# cc_cv_charger.net
KiCad netlist of a schematic drawn in Altium Designer
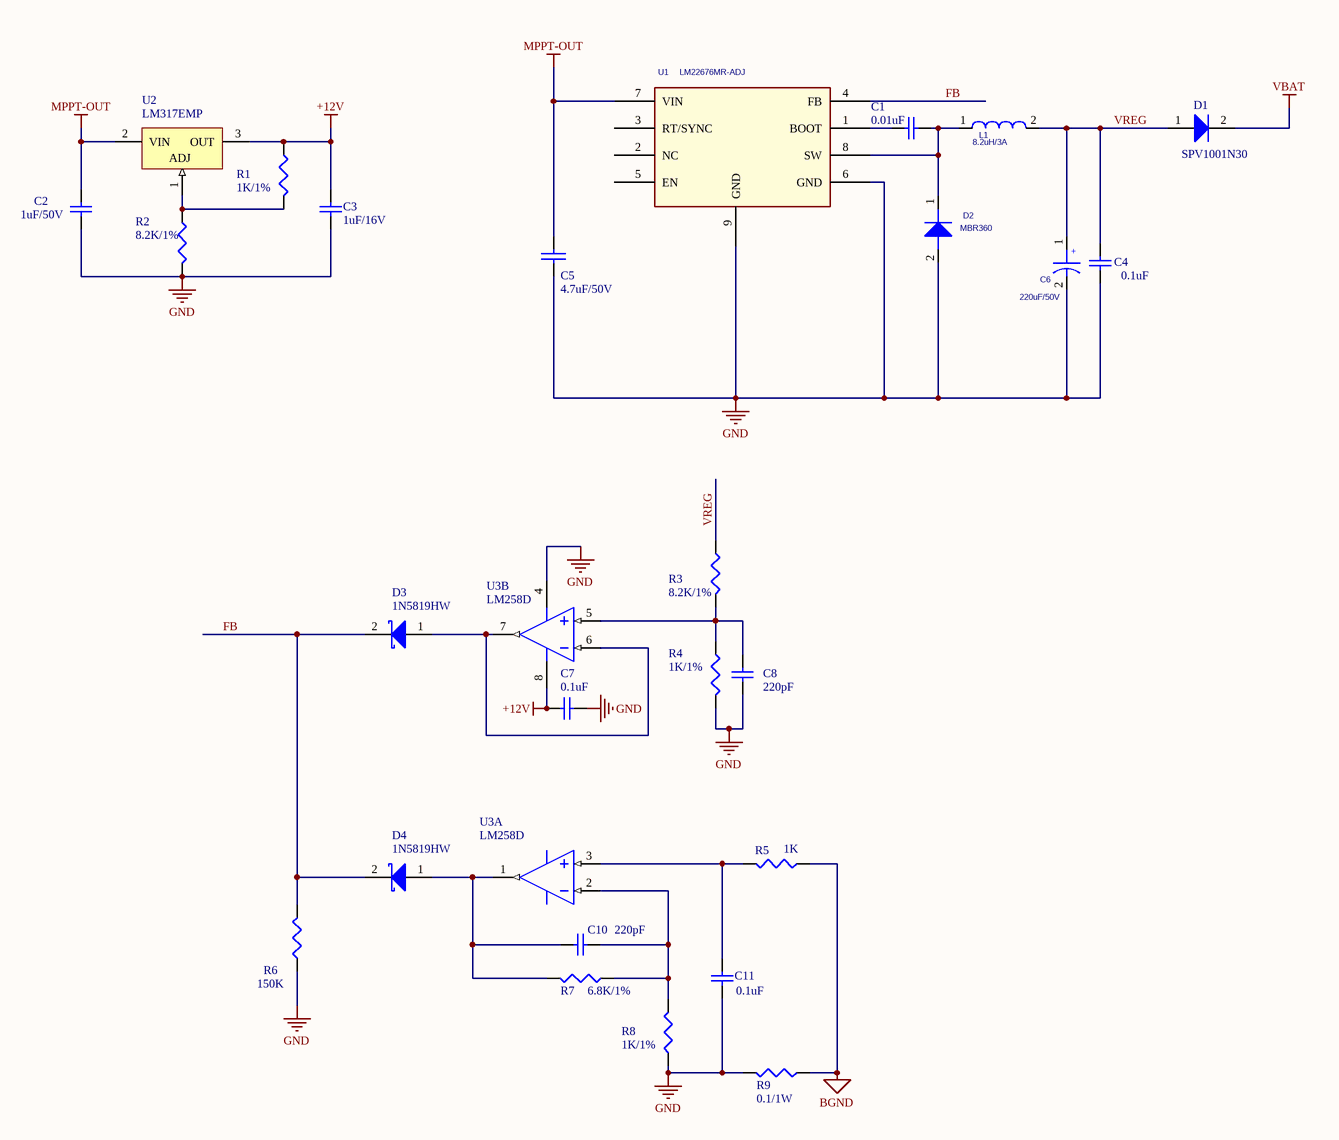
[diagram p0: cc_cv_charger.SchDoc]

(export (version "E")
  (design (tool "Eeschema 10.0.6"))
  (components
    (comp (ref "C1")
      (value "0.01uF")
      (footprint "0603")
      (description "Capacitor")
      (fields (field (name "PUBLISHER") "Altium Limited"))
      (libsource (lib "Miscellaneous Devices") (part "Cap"))
    )
    (comp (ref "C2")
      (value "1uF/50V")
      (footprint "1210")
      (description "Capacitor")
      (fields (field (name "PUBLISHER") "Altium Limited"))
      (libsource (lib "Miscellaneous Devices") (part "Cap"))
    )
    (comp (ref "C3")
      (value "1uF/16V")
      (footprint "0805")
      (description "Capacitor")
      (fields (field (name "PUBLISHER") "Altium Limited"))
      (libsource (lib "Miscellaneous Devices") (part "Cap"))
    )
    (comp (ref "C4")
      (value "0.1uF")
      (footprint "0603")
      (description "Capacitor")
      (fields (field (name "PUBLISHER") "Altium Limited"))
      (libsource (lib "Miscellaneous Devices") (part "Cap"))
    )
    (comp (ref "C5")
      (value "4.7uF/50V")
      (footprint "1812")
      (description "Capacitor")
      (libsource (lib "*") (part "CAP"))
    )
    (comp (ref "C6") (value "220uF/50V") (libsource (lib "*") (part "CAP WP")))
    (comp (ref "C7")
      (value "0.1uF")
      (footprint "0603")
      (description "Capacitor")
      (fields (field (name "PUBLISHER") "Altium Limited"))
      (libsource (lib "Miscellaneous Devices") (part "Cap"))
    )
    (comp (ref "C8")
      (value "220pF")
      (footprint "0603")
      (description "Capacitor")
      (fields (field (name "PUBLISHER") "Altium Limited"))
      (libsource (lib "Miscellaneous Devices") (part "Cap"))
    )
    (comp (ref "C10")
      (value "220pF")
      (footprint "0603")
      (description "Capacitor")
      (fields (field (name "PUBLISHER") "Altium Limited"))
      (libsource (lib "Miscellaneous Devices") (part "Cap"))
    )
    (comp (ref "C11")
      (value "0.1uF")
      (footprint "0603")
      (description "Capacitor")
      (fields (field (name "PUBLISHER") "Altium Limited"))
      (libsource (lib "Miscellaneous Devices") (part "Cap"))
    )
    (comp (ref "D1")
      (value "SPV1001N30")
      (footprint "SPV1001")
      (description "Default Diode")
      (fields (field (name "PUBLISHER") "Altium Limited"))
      (libsource (lib "Miscellaneous Devices") (part "Diode"))
    )
    (comp (ref "D2")
      (value "MBR360")
      (footprint "DO214AB")
      (libsource (lib "*") (part "1N4148WS-7-F_SOD323-2"))
    )
    (comp (ref "D3")
      (value "1N5819HW")
      (footprint "1N5819")
      (description "Schottky Rectifier")
      (libsource (lib "Miscellaneous Devices") (part "Diode 11DQ03"))
    )
    (comp (ref "D4")
      (value "1N5819HW")
      (footprint "1N5819")
      (description "Schottky Rectifier")
      (libsource (lib "Miscellaneous Devices") (part "Diode 11DQ03"))
    )
    (comp (ref "L1")
      (value "8.2uH/3A")
      (footprint "IND_8.2UH_3A")
      (fields (field (name "PART NUMBER") "SH00000AJ00"))
      (libsource (lib "*") (part "4.7UH_CDH2D09BNP-4R7MC_0.7A_20%"))
    )
    (comp (ref "R1")
      (value "1K/1%")
      (footprint "0603")
      (description "Resistor")
      (fields (field (name "PUBLISHER") "Altium Limited"))
      (libsource (lib "Miscellaneous Devices") (part "Res3"))
    )
    (comp (ref "R2")
      (value "8.2K/1%")
      (footprint "0603")
      (description "Resistor")
      (fields (field (name "PUBLISHER") "Altium Limited"))
      (libsource (lib "Miscellaneous Devices") (part "Res3"))
    )
    (comp (ref "R3")
      (value "8.2K/1%")
      (footprint "0603")
      (description "Resistor")
      (fields (field (name "PUBLISHER") "Altium Limited"))
      (libsource (lib "Miscellaneous Devices") (part "Res3"))
    )
    (comp (ref "R4")
      (value "1K/1%")
      (footprint "0603")
      (description "Resistor")
      (fields (field (name "PUBLISHER") "Altium Limited"))
      (libsource (lib "Miscellaneous Devices") (part "Res3"))
    )
    (comp (ref "R5")
      (value "1K")
      (footprint "0603")
      (description "Resistor")
      (fields (field (name "PUBLISHER") "Altium Limited"))
      (libsource (lib "Miscellaneous Devices") (part "Res3"))
    )
    (comp (ref "R6")
      (value "150K")
      (footprint "0603")
      (description "Resistor")
      (fields (field (name "PUBLISHER") "Altium Limited"))
      (libsource (lib "Miscellaneous Devices") (part "Res3"))
    )
    (comp (ref "R7")
      (value "6.8K/1%")
      (footprint "0603")
      (description "Resistor")
      (fields (field (name "PUBLISHER") "Altium Limited"))
      (libsource (lib "Miscellaneous Devices") (part "Res3"))
    )
    (comp (ref "R8")
      (value "1K/1%")
      (footprint "0603")
      (description "Resistor")
      (fields (field (name "PUBLISHER") "Altium Limited"))
      (libsource (lib "Miscellaneous Devices") (part "Res3"))
    )
    (comp (ref "R9")
      (value "0.1/1W")
      (footprint "2512")
      (description "Resistor")
      (fields (field (name "PUBLISHER") "Altium Limited"))
      (libsource (lib "Miscellaneous Devices") (part "Res3"))
    )
    (comp (ref "U1") (value "LM22676MR-ADJ") (libsource (lib "*") (part "LM22670_0")))
    (comp (ref "U2")
      (value "LM317EMP")
      (footprint "LM317")
      (description "3-Terminal Adjustable Regulator, 3-pin TO-3")
      (fields
        (field (name "PARTNUMBER") "LM317K STEEL")
        (field (name "MANUFACTURER") "National Semiconductor")
        (field (name "PUBLISHER") "Altium Limited")
      )
      (libsource (lib "NSC MiscPower") (part "LM317K STEEL"))
    )
    (comp (ref "U3")
      (value "LM258D")
      (footprint "SO8")
      (description "Low Power Dual Operational Amplifier, 8-pin TO-99")
      (fields
        (field (name "PARTNUMBER") "LM258H")
        (field (name "MANUFACTURER") "National Semiconductor")
        (field (name "PUBLISHER") "Altium Limited")
      )
      (libsource (lib "NSC Amplifier") (part "LM258H"))
    )
  )
  (nets
    (net (code "1") (name "+12V") (class "Default")
      (node (ref "C3") (pin "2") (pinfunction "2_2") (pintype "passive"))
      (node (ref "C7") (pin "2") (pinfunction "2_2") (pintype "passive"))
      (node (ref "R1") (pin "1") (pinfunction "1_1") (pintype "passive"))
      (node (ref "U2") (pin "3") (pinfunction "OUT_3") (pintype "power_in"))
      (node (ref "U3") (pin "8") (pinfunction "V+_8") (pintype "power_in"))
    )
    (net (code "2") (name "/FB") (class "Default")
      (node (ref "D3") (pin "2") (pinfunction "K_2") (pintype "passive"))
      (node (ref "D4") (pin "2") (pinfunction "K_2") (pintype "passive"))
      (node (ref "R6") (pin "2") (pinfunction "2_2") (pintype "passive"))
      (node (ref "U1") (pin "4") (pinfunction "FB_4") (pintype "passive"))
    )
    (net (code "3") (name "/VREG") (class "Default")
      (node (ref "C4") (pin "2") (pinfunction "2_2") (pintype "passive"))
      (node (ref "C6") (pin "1") (pinfunction "1_1") (pintype "passive"))
      (node (ref "D1") (pin "1") (pinfunction "A_1") (pintype "passive"))
      (node (ref "L1") (pin "2") (pinfunction "2_2") (pintype "passive"))
      (node (ref "R3") (pin "1") (pinfunction "1_1") (pintype "passive"))
    )
    (net (code "4") (name "BGND") (class "Default")
      (node (ref "R5") (pin "1") (pinfunction "1_1") (pintype "passive"))
      (node (ref "R9") (pin "1") (pinfunction "1_1") (pintype "passive"))
    )
    (net (code "5") (name "GND") (class "Default")
      (node (ref "C11") (pin "2") (pinfunction "2_2") (pintype "passive"))
      (node (ref "C2") (pin "1") (pinfunction "1_1") (pintype "passive"))
      (node (ref "C3") (pin "1") (pinfunction "1_1") (pintype "passive"))
      (node (ref "C4") (pin "1") (pinfunction "1_1") (pintype "passive"))
      (node (ref "C5") (pin "2") (pinfunction "2_2") (pintype "passive"))
      (node (ref "C6") (pin "2") (pinfunction "2_2") (pintype "passive"))
      (node (ref "C7") (pin "1") (pinfunction "1_1") (pintype "passive"))
      (node (ref "C8") (pin "2") (pinfunction "2_2") (pintype "passive"))
      (node (ref "D2") (pin "2") (pinfunction "2_2") (pintype "passive"))
      (node (ref "R2") (pin "2") (pinfunction "2_2") (pintype "passive"))
      (node (ref "R4") (pin "2") (pinfunction "2_2") (pintype "passive"))
      (node (ref "R6") (pin "1") (pinfunction "1_1") (pintype "passive"))
      (node (ref "R8") (pin "1") (pinfunction "1_1") (pintype "passive"))
      (node (ref "R9") (pin "2") (pinfunction "2_2") (pintype "passive"))
      (node (ref "U1") (pin "6") (pinfunction "GND_6") (pintype "passive"))
      (node (ref "U1") (pin "9") (pinfunction "GND_9") (pintype "power_in"))
      (node (ref "U3") (pin "4") (pinfunction "GND_4") (pintype "power_in"))
    )
    (net (code "6") (name "MPPT-OUT") (class "Default")
      (node (ref "C2") (pin "2") (pinfunction "2_2") (pintype "passive"))
      (node (ref "C5") (pin "1") (pinfunction "1_1") (pintype "passive"))
      (node (ref "U1") (pin "7") (pinfunction "VIN_7") (pintype "power_in"))
      (node (ref "U2") (pin "2") (pinfunction "VIN_2") (pintype "power_in"))
    )
    (net (code "7") (name "Net-(D3-A)") (class "Default")
      (node (ref "D3") (pin "1") (pinfunction "A_1") (pintype "passive"))
      (node (ref "U3") (pin "6") (pinfunction "INB-_6") (pintype "input"))
      (node (ref "U3") (pin "7") (pinfunction "OUTB_7") (pintype "output"))
    )
    (net (code "8") (name "Net-(D4-A)") (class "Default")
      (node (ref "C10") (pin "2") (pinfunction "2_2") (pintype "passive"))
      (node (ref "D4") (pin "1") (pinfunction "A_1") (pintype "passive"))
      (node (ref "R7") (pin "2") (pinfunction "2_2") (pintype "passive"))
      (node (ref "U3") (pin "1") (pinfunction "OUTA_1") (pintype "output"))
    )
    (net (code "9") (name "Net-(U1-BOOT)") (class "Default")
      (node (ref "C1") (pin "2") (pinfunction "2_2") (pintype "passive"))
      (node (ref "U1") (pin "1") (pinfunction "BOOT_1") (pintype "passive"))
    )
    (net (code "10") (name "Net-(U1-SW)") (class "Default")
      (node (ref "C1") (pin "1") (pinfunction "1_1") (pintype "passive"))
      (node (ref "D2") (pin "1") (pinfunction "1_1") (pintype "passive"))
      (node (ref "L1") (pin "1") (pinfunction "1_1") (pintype "passive"))
      (node (ref "U1") (pin "8") (pinfunction "SW_8") (pintype "passive"))
    )
    (net (code "11") (name "Net-(U2-ADJ)") (class "Default")
      (node (ref "R1") (pin "2") (pinfunction "2_2") (pintype "passive"))
      (node (ref "R2") (pin "1") (pinfunction "1_1") (pintype "passive"))
      (node (ref "U2") (pin "1") (pinfunction "ADJ_1") (pintype "input"))
    )
    (net (code "12") (name "Net-(U3A-INA+)") (class "Default")
      (node (ref "C11") (pin "1") (pinfunction "1_1") (pintype "passive"))
      (node (ref "R5") (pin "2") (pinfunction "2_2") (pintype "passive"))
      (node (ref "U3") (pin "3") (pinfunction "INA+_3") (pintype "input"))
    )
    (net (code "13") (name "Net-(U3A-INA-)") (class "Default")
      (node (ref "C10") (pin "1") (pinfunction "1_1") (pintype "passive"))
      (node (ref "R7") (pin "1") (pinfunction "1_1") (pintype "passive"))
      (node (ref "R8") (pin "2") (pinfunction "2_2") (pintype "passive"))
      (node (ref "U3") (pin "2") (pinfunction "INA-_2") (pintype "input"))
    )
    (net (code "14") (name "Net-(U3B-INB+)") (class "Default")
      (node (ref "C8") (pin "1") (pinfunction "1_1") (pintype "passive"))
      (node (ref "R3") (pin "2") (pinfunction "2_2") (pintype "passive"))
      (node (ref "R4") (pin "1") (pinfunction "1_1") (pintype "passive"))
      (node (ref "U3") (pin "5") (pinfunction "INB+_5") (pintype "input"))
    )
    (net (code "15") (name "VBAT") (class "Default")
      (node (ref "D1") (pin "2") (pinfunction "K_2") (pintype "passive"))
    )
    (net (code "16") (name "unconnected-(U1-EN-Pad5)") (class "Default")
      (node (ref "U1") (pin "5") (pinfunction "EN_5") (pintype "passive"))
    )
    (net (code "17") (name "unconnected-(U1-NC-Pad2)") (class "Default")
      (node (ref "U1") (pin "2") (pinfunction "NC_2") (pintype "passive"))
    )
    (net (code "18") (name "unconnected-(U1-RT{slash}SYNC-Pad3)") (class "Default")
      (node (ref "U1") (pin "3") (pinfunction "RT/SYNC_3") (pintype "passive"))
    )
    (net (code "19") (name "unconnected-(U3A-GND-Pad4)") (class "Default")
      (node (ref "U3") (pin "4") (pinfunction "GND_4") (pintype "power_in"))
    )
    (net (code "20") (name "unconnected-(U3A-V+-Pad8)") (class "Default")
      (node (ref "U3") (pin "8") (pinfunction "V+_8") (pintype "power_in"))
    )
  )
)
